# PM-BAT_v0_4-35X22_86.net
KiCad netlist of a schematic drawn in EAGLE
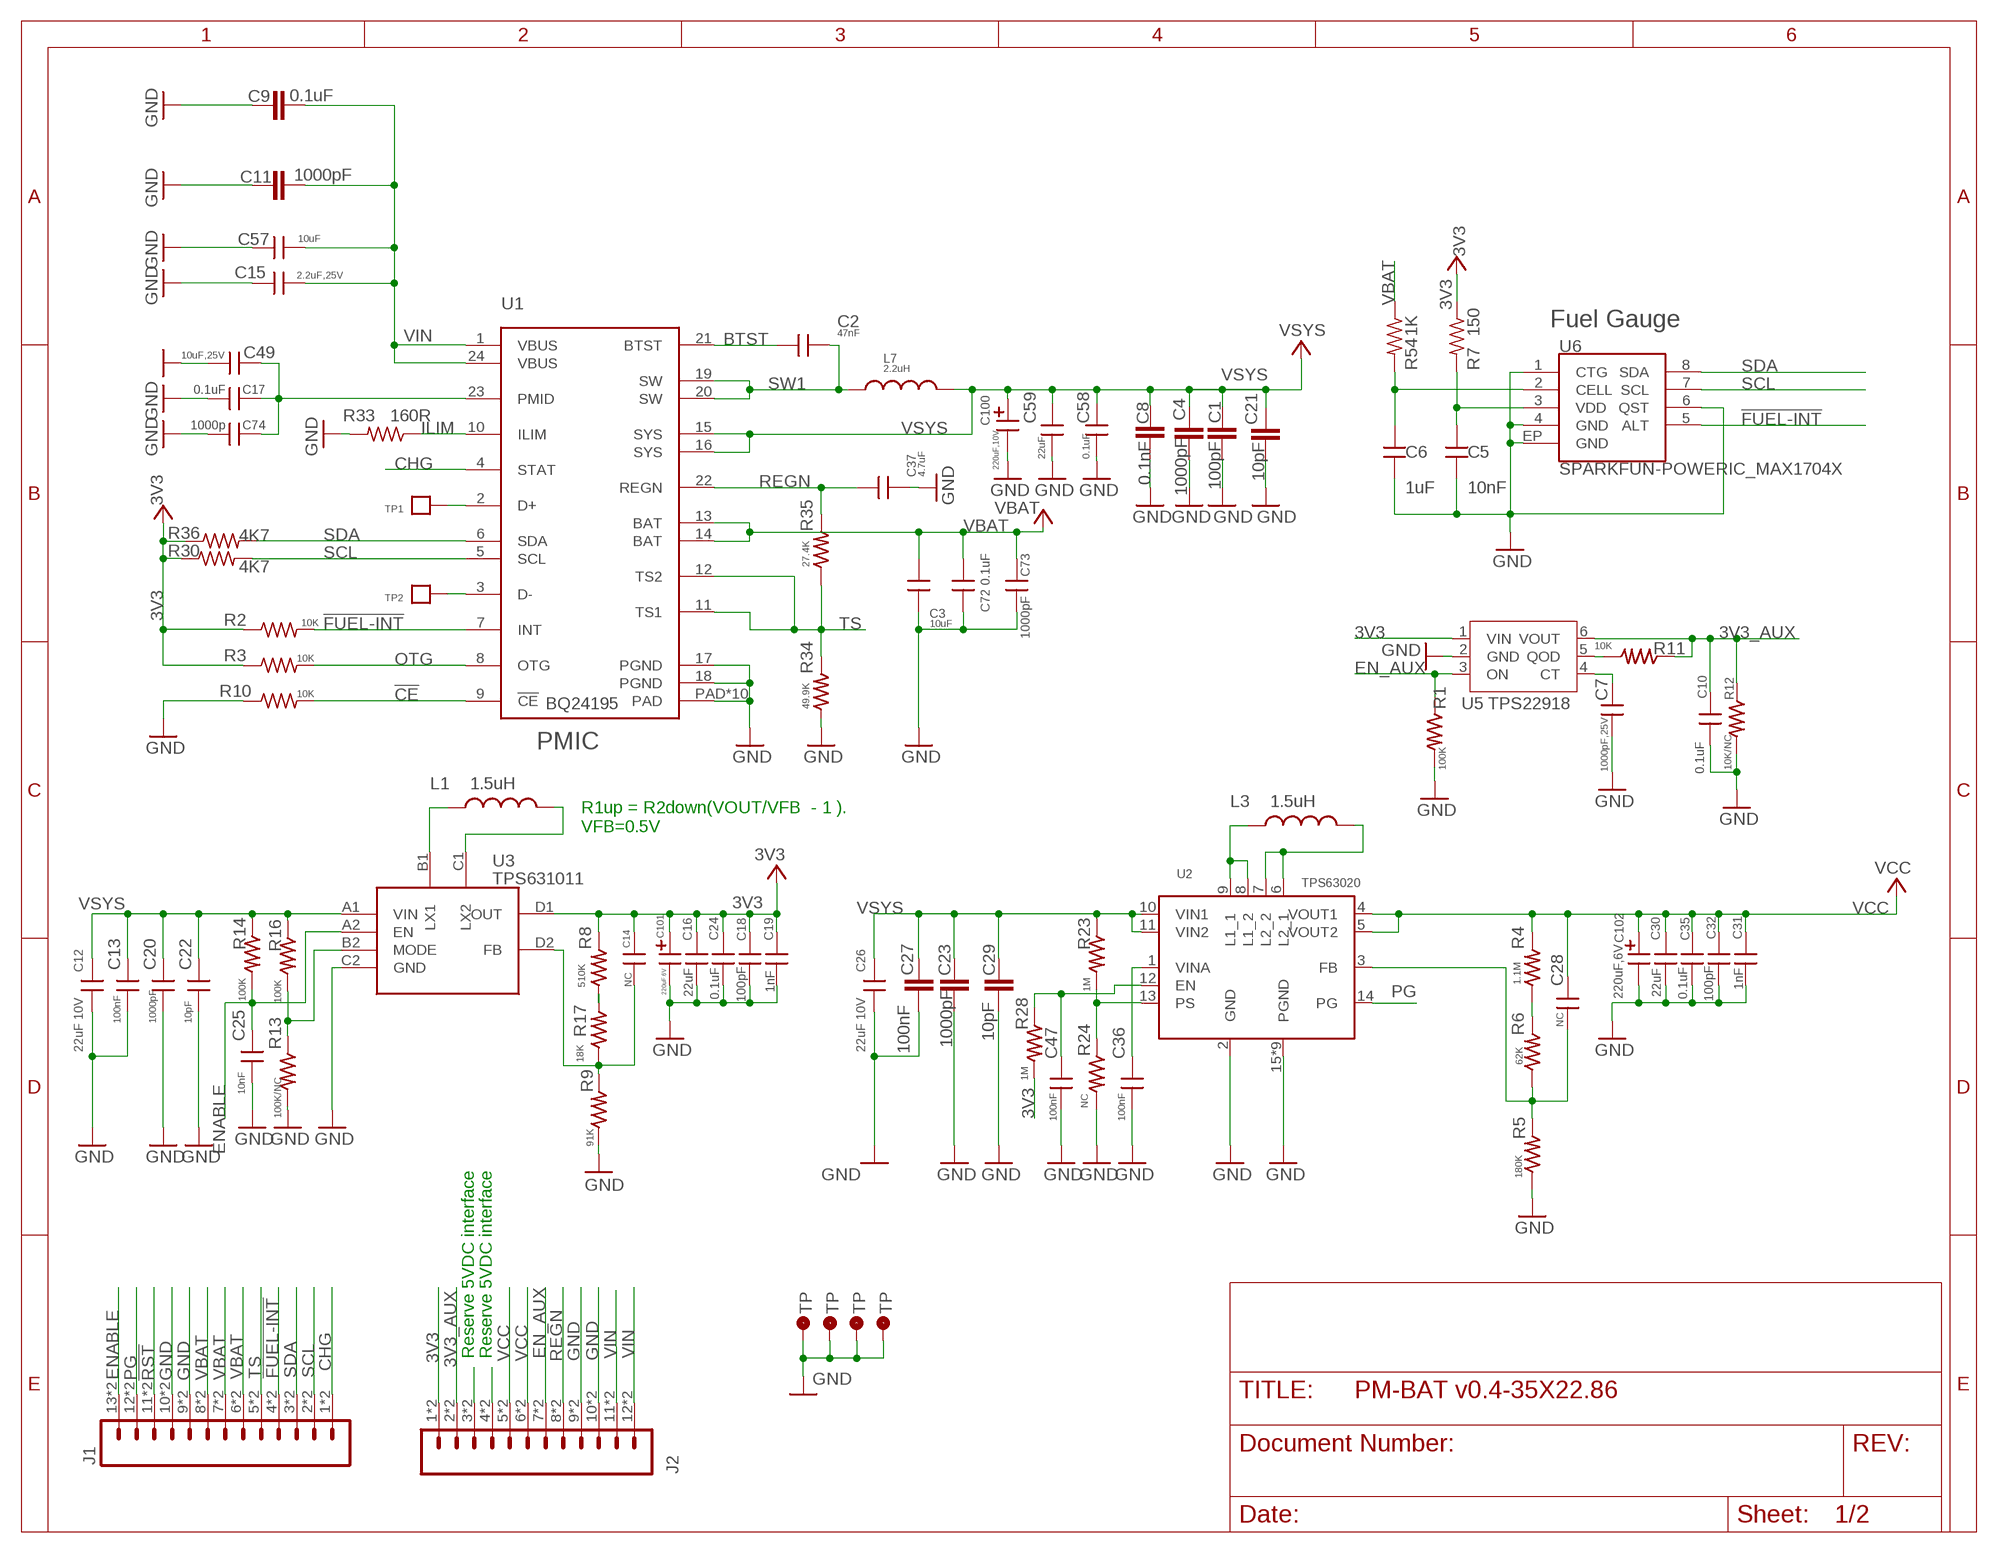
[diagram p0: schematic, sheet 1]

(export (version "E")
  (design (tool "Eeschema 10.0.6"))
  (components
    (comp (ref "C1")
      (value "100pF")
      (footprint "eagle-import:C0402_B")
      (libsource (lib "eagle-import") (part "CAP_1"))
    )
    (comp (ref "C2")
      (value "47nF")
      (footprint "eagle-import:C-0402")
      (libsource (lib "eagle-import") (part "particle SZ_CAP0402"))
    )
    (comp (ref "C3")
      (value "10uF")
      (footprint "eagle-import:C0805")
      (libsource (lib "eagle-import") (part "particle SZ_CAPC0805"))
    )
    (comp (ref "C4")
      (value "1000pF")
      (footprint "eagle-import:C0402_B")
      (libsource (lib "eagle-import") (part "CAP_1"))
    )
    (comp (ref "C5")
      (value "10nF")
      (footprint "eagle-import:C0402")
      (libsource (lib "eagle-import") (part "particle SZ_CAP0402A"))
    )
    (comp (ref "C6")
      (value "1uF")
      (footprint "eagle-import:C0402")
      (libsource (lib "eagle-import") (part "particle SZ_CAP0402A"))
    )
    (comp (ref "C7")
      (value "1000pF,25V")
      (footprint "eagle-import:C0402")
      (libsource (lib "eagle-import") (part "particle SZ_CAP0402A"))
    )
    (comp (ref "C8")
      (value "0.1nF")
      (footprint "eagle-import:C0402_B")
      (libsource (lib "eagle-import") (part "CAP_1"))
    )
    (comp (ref "C9")
      (value "0.1uF")
      (footprint "eagle-import:C0402_B")
      (libsource (lib "eagle-import") (part "CAP_1"))
    )
    (comp (ref "C10")
      (value "0.1uF")
      (footprint "eagle-import:C0201-N")
      (libsource (lib "eagle-import") (part "CAPC0201-N"))
    )
    (comp (ref "C11")
      (value "1000pF")
      (footprint "eagle-import:C0402_B")
      (libsource (lib "eagle-import") (part "CAP_1"))
    )
    (comp (ref "C12")
      (value "22uF 10V")
      (footprint "eagle-import:C0603")
      (libsource (lib "eagle-import") (part "particle SZ_21650216_CAPC0603"))
    )
    (comp (ref "C13")
      (value "100nF")
      (footprint "eagle-import:C0201-N")
      (libsource (lib "eagle-import") (part "CAPC0201-N"))
    )
    (comp (ref "C14")
      (value "NC")
      (footprint "eagle-import:C0201-N")
      (libsource (lib "eagle-import") (part "CAPC0201-N"))
    )
    (comp (ref "C15")
      (value "2.2uF,25V")
      (footprint "eagle-import:C-0603A")
      (libsource (lib "eagle-import") (part "particle SZ_CAP0603A"))
    )
    (comp (ref "C16")
      (value "22uF")
      (footprint "eagle-import:C-0603A")
      (libsource (lib "eagle-import") (part "particle SZ_21650216_CAP0603A"))
    )
    (comp (ref "C17")
      (value "0.1uF")
      (footprint "eagle-import:C0402")
      (libsource (lib "eagle-import") (part "CAP0402A"))
    )
    (comp (ref "C18")
      (value "100pF")
      (footprint "eagle-import:C0402")
      (libsource (lib "eagle-import") (part "particle SZ_CAP0402A"))
    )
    (comp (ref "C19")
      (value "1nF")
      (footprint "eagle-import:C0402")
      (libsource (lib "eagle-import") (part "particle SZ_CAP0402A"))
    )
    (comp (ref "C20")
      (value "1000pF")
      (footprint "eagle-import:C0201-N")
      (libsource (lib "eagle-import") (part "CAPC0201-N"))
    )
    (comp (ref "C21")
      (value "10pF")
      (footprint "eagle-import:C0402_B")
      (libsource (lib "eagle-import") (part "CAP_1"))
    )
    (comp (ref "C22")
      (value "10pF")
      (footprint "eagle-import:C0201-N")
      (libsource (lib "eagle-import") (part "CAPC0201-N"))
    )
    (comp (ref "C23")
      (value "1000pF")
      (footprint "eagle-import:C0402_B")
      (libsource (lib "eagle-import") (part "CAP_1"))
    )
    (comp (ref "C24")
      (value "0.1uF")
      (footprint "eagle-import:C0402")
      (libsource (lib "eagle-import") (part "particle SZ_CAP0402A"))
    )
    (comp (ref "C25")
      (value "10nF")
      (footprint "eagle-import:C0201-N")
      (libsource (lib "eagle-import") (part "CAPC0201-N"))
    )
    (comp (ref "C26")
      (value "22uF 10V")
      (footprint "eagle-import:C0603")
      (libsource (lib "eagle-import") (part "particle SZ_21650216_CAPC0603"))
    )
    (comp (ref "C27")
      (value "100nF")
      (footprint "eagle-import:C0402_B")
      (libsource (lib "eagle-import") (part "CAP_1"))
    )
    (comp (ref "C28")
      (value "NC")
      (footprint "eagle-import:C0201-N")
      (libsource (lib "eagle-import") (part "CAPC0201-N"))
    )
    (comp (ref "C29")
      (value "10pF")
      (footprint "eagle-import:C0402_B")
      (libsource (lib "eagle-import") (part "CAP_1"))
    )
    (comp (ref "C30")
      (value "22uF")
      (footprint "eagle-import:C-0603A")
      (libsource (lib "eagle-import") (part "particle SZ_21650216_CAP0603A"))
    )
    (comp (ref "C31")
      (value "1nF")
      (footprint "eagle-import:C0402")
      (libsource (lib "eagle-import") (part "particle SZ_CAP0402A"))
    )
    (comp (ref "C32")
      (value "100pF")
      (footprint "eagle-import:C0402")
      (libsource (lib "eagle-import") (part "particle SZ_CAP0402A"))
    )
    (comp (ref "C35")
      (value "0.1uF")
      (footprint "eagle-import:C0402")
      (libsource (lib "eagle-import") (part "particle SZ_CAP0402A"))
    )
    (comp (ref "C36")
      (value "100nF")
      (footprint "eagle-import:C0201-N")
      (libsource (lib "eagle-import") (part "CAPC0201-N"))
    )
    (comp (ref "C37")
      (value "4.7uF")
      (footprint "eagle-import:C0402")
      (libsource (lib "eagle-import") (part "particle SZ_CAP0402A"))
    )
    (comp (ref "C47")
      (value "100nF")
      (footprint "eagle-import:C0201-N")
      (libsource (lib "eagle-import") (part "CAPC0201-N"))
    )
    (comp (ref "C49")
      (value "10uF,25V")
      (footprint "eagle-import:C-0603A")
      (libsource (lib "eagle-import") (part "particle SZ_CAP0603A"))
    )
    (comp (ref "C57")
      (value "10uF")
      (footprint "eagle-import:C-0603A")
      (libsource (lib "eagle-import") (part "particle SZ_CAP0603A"))
    )
    (comp (ref "C58")
      (value "0.1uF")
      (footprint "eagle-import:C0402")
      (libsource (lib "eagle-import") (part "particle SZ_CAP0402A"))
    )
    (comp (ref "C59")
      (value "22uF")
      (footprint "eagle-import:C0603")
      (libsource (lib "eagle-import") (part "particle SZ_CAPC0603"))
    )
    (comp (ref "C72")
      (value "0.1uF")
      (footprint "eagle-import:C-0402")
      (libsource (lib "eagle-import") (part "particle SZ_CAP0402"))
    )
    (comp (ref "C73")
      (value "1000pF")
      (footprint "eagle-import:C-0402")
      (libsource (lib "eagle-import") (part "particle SZ_CAP0402"))
    )
    (comp (ref "C74")
      (value "1000p")
      (footprint "eagle-import:C-0402")
      (libsource (lib "eagle-import") (part "particle SZ_CAP0402"))
    )
    (comp (ref "C100")
      (value "220uF,10V")
      (footprint "eagle-import:CASE-B")
      (libsource (lib "eagle-import") (part "CAP-ECASE_B"))
    )
    (comp (ref "C101")
      (value "220uF.6V")
      (footprint "eagle-import:CASE-B")
      (libsource (lib "eagle-import") (part "CAP-ECASE_B"))
    )
    (comp (ref "C102")
      (value "220uF,6V")
      (footprint "eagle-import:CASE-B")
      (libsource (lib "eagle-import") (part "CAP-ECASE_B"))
    )
    (comp (ref "J1")
      (value "M13PTH-CST-R")
      (footprint "eagle-import:1X13-CASTELLATED")
      (libsource (lib "eagle-import") (part "M13PTH-CST-R"))
    )
    (comp (ref "J2")
      (value "M12PTH-CST-R")
      (footprint "eagle-import:1X12-CASTELLATED")
      (libsource (lib "eagle-import") (part "M12PTH-CST-R"))
    )
    (comp (ref "L1")
      (value "1.5uH")
      (footprint "eagle-import:INDUCTOR-2520")
      (libsource (lib "eagle-import") (part "INDUCTOR-SPARKFUNINDUCTOR-2520"))
    )
    (comp (ref "L3")
      (value "1.5uH")
      (footprint "eagle-import:INDUCTOR-2520")
      (libsource (lib "eagle-import") (part "INDUCTOR-SPARKFUNINDUCTOR-2520"))
    )
    (comp (ref "L7")
      (value "2.2uH")
      (footprint "eagle-import:INDUCTOR-4040")
      (libsource (lib "eagle-import") (part "INDUCTORI"))
    )
    (comp (ref "R1")
      (value "100K")
      (footprint "eagle-import:R0201-N")
      (libsource (lib "eagle-import") (part "RESR0201-N"))
    )
    (comp (ref "R2")
      (value "10K")
      (footprint "eagle-import:R0402_B")
      (libsource (lib "eagle-import") (part "Spark_R-US_"))
    )
    (comp (ref "R3")
      (value "10K")
      (footprint "eagle-import:R0402_B")
      (libsource (lib "eagle-import") (part "Spark_R-US_"))
    )
    (comp (ref "R4")
      (value "1.1M")
      (footprint "eagle-import:R0201-N")
      (libsource (lib "eagle-import") (part "RESR0201-N"))
    )
    (comp (ref "R5")
      (value "180K")
      (footprint "eagle-import:R0201-N")
      (libsource (lib "eagle-import") (part "RESR0201-N"))
    )
    (comp (ref "R6")
      (value "62K")
      (footprint "eagle-import:R0201-N")
      (libsource (lib "eagle-import") (part "RESR0201-N"))
    )
    (comp (ref "R7")
      (value "150")
      (footprint "eagle-import:R0402_B")
      (libsource (lib "eagle-import") (part "R-US_"))
    )
    (comp (ref "R8")
      (value "510K")
      (footprint "eagle-import:R0201-N")
      (libsource (lib "eagle-import") (part "RESR0201-N"))
    )
    (comp (ref "R9")
      (value "91K")
      (footprint "eagle-import:R0201-N")
      (libsource (lib "eagle-import") (part "RESR0201-N"))
    )
    (comp (ref "R10")
      (value "10K")
      (footprint "eagle-import:R0402_B")
      (libsource (lib "eagle-import") (part "Spark_R-US_"))
    )
    (comp (ref "R11")
      (value "10K")
      (footprint "eagle-import:R0201-N")
      (libsource (lib "eagle-import") (part "RESR0201-N"))
    )
    (comp (ref "R12")
      (value "10K/NC")
      (footprint "eagle-import:R0201-N")
      (libsource (lib "eagle-import") (part "RESR0201-N"))
    )
    (comp (ref "R13")
      (value "100K/NC")
      (footprint "eagle-import:R0201-N")
      (libsource (lib "eagle-import") (part "RESR0201-N"))
    )
    (comp (ref "R14")
      (value "100K")
      (footprint "eagle-import:R0201-N")
      (libsource (lib "eagle-import") (part "RESR0201-N"))
    )
    (comp (ref "R16")
      (value "100K")
      (footprint "eagle-import:R0201-N")
      (libsource (lib "eagle-import") (part "RESR0201-N"))
    )
    (comp (ref "R17")
      (value "18K")
      (footprint "eagle-import:R0201-N")
      (libsource (lib "eagle-import") (part "RESR0201-N"))
    )
    (comp (ref "R23")
      (value "1M")
      (footprint "eagle-import:R0201-N")
      (libsource (lib "eagle-import") (part "RESR0201-N"))
    )
    (comp (ref "R24")
      (value "NC")
      (footprint "eagle-import:R0201-N")
      (libsource (lib "eagle-import") (part "RESR0201-N"))
    )
    (comp (ref "R28")
      (value "1M")
      (footprint "eagle-import:R0201-N")
      (libsource (lib "eagle-import") (part "RESR0201-N"))
    )
    (comp (ref "R30")
      (value "4K7")
      (footprint "eagle-import:R0402_B")
      (libsource (lib "eagle-import") (part "R-US_"))
    )
    (comp (ref "R33")
      (value "160R")
      (footprint "eagle-import:R0402_B")
      (libsource (lib "eagle-import") (part "R-US_"))
    )
    (comp (ref "R34")
      (value "49.9K")
      (footprint "eagle-import:R0201-N")
      (libsource (lib "eagle-import") (part "RESR0201-N"))
    )
    (comp (ref "R35")
      (value "27.4K")
      (footprint "eagle-import:R0201-N")
      (libsource (lib "eagle-import") (part "RESR0201-N"))
    )
    (comp (ref "R36")
      (value "4K7")
      (footprint "eagle-import:R0402_B")
      (libsource (lib "eagle-import") (part "R-US_"))
    )
    (comp (ref "R54")
      (value "1K")
      (footprint "eagle-import:R0402_B")
      (libsource (lib "eagle-import") (part "R-US_"))
    )
    (comp (ref "TP1")
      (value "TP1311MM")
      (footprint "eagle-import:TP-1311MM")
      (libsource (lib "eagle-import") (part "TP1311MM"))
    )
    (comp (ref "TP2")
      (value "TP1311MM")
      (footprint "eagle-import:TP-1311MM")
      (libsource (lib "eagle-import") (part "TP1311MM"))
    )
    (comp (ref "U$1")
      (value "TP")
      (footprint "eagle-import:TP_2.33X1.37")
      (libsource (lib "eagle-import") (part "TP"))
    )
    (comp (ref "U$2")
      (value "TP")
      (footprint "eagle-import:TP_2.33X1.37")
      (libsource (lib "eagle-import") (part "TP"))
    )
    (comp (ref "U$4")
      (value "TP")
      (footprint "eagle-import:TP_2.33X1.37")
      (libsource (lib "eagle-import") (part "TP"))
    )
    (comp (ref "U$5")
      (value "TP")
      (footprint "eagle-import:TP_2.33X1.37")
      (libsource (lib "eagle-import") (part "TP"))
    )
    (comp (ref "U1")
      (value "BQ24195")
      (footprint "eagle-import:ELECTRON_QFN24")
      (libsource (lib "eagle-import") (part "ELECTRON_BQ24298RTWR"))
    )
    (comp (ref "U2")
      (value "TPS63020")
      (footprint "eagle-import:TPS63020")
      (libsource (lib "eagle-import") (part "TPS63020"))
    )
    (comp (ref "U3")
      (value "TPS631011")
      (footprint "eagle-import:DSBGA")
      (libsource (lib "eagle-import") (part "TPS631010"))
    )
    (comp (ref "U5")
      (value "TPS22918")
      (footprint "eagle-import:SOT-23-6")
      (libsource (lib "eagle-import") (part "TPS22918"))
    )
    (comp (ref "U6")
      (value "SPARKFUN-POWERIC_MAX1704X")
      (footprint "eagle-import:SPARKFUN-POWERIC_TDFN-8")
      (libsource (lib "eagle-import") (part "SPARKFUN-POWERIC_MAX1704X"))
    )
  )
  (nets
    (net (code "1") (name "3V3") (class "Default")
      (node (ref "C101") (pin "P$1") (pinfunction "1_P$1") (pintype "bidirectional"))
      (node (ref "C14") (pin "1") (pinfunction "1_1") (pintype "bidirectional"))
      (node (ref "C16") (pin "1") (pinfunction "1_1") (pintype "bidirectional"))
      (node (ref "C18") (pin "1") (pinfunction "1_1") (pintype "bidirectional"))
      (node (ref "C19") (pin "1") (pinfunction "1_1") (pintype "bidirectional"))
      (node (ref "C24") (pin "1") (pinfunction "1_1") (pintype "bidirectional"))
      (node (ref "J2") (pin "1") (pinfunction "1_1") (pintype "passive"))
      (node (ref "J2") (pin "@1") (pinfunction "1_@1") (pintype "passive"))
      (node (ref "R2") (pin "1") (pinfunction "1_1") (pintype "passive"))
      (node (ref "R28") (pin "2") (pinfunction "2_2") (pintype "bidirectional"))
      (node (ref "R3") (pin "1") (pinfunction "1_1") (pintype "passive"))
      (node (ref "R30") (pin "1") (pinfunction "1_1") (pintype "passive"))
      (node (ref "R36") (pin "1") (pinfunction "1_1") (pintype "passive"))
      (node (ref "R7") (pin "1") (pinfunction "1_1") (pintype "passive"))
      (node (ref "R8") (pin "2") (pinfunction "2_2") (pintype "bidirectional"))
      (node (ref "U3") (pin "D1") (pinfunction "OUT_D1") (pintype "bidirectional"))
      (node (ref "U5") (pin "1") (pinfunction "VIN_1") (pintype "bidirectional"))
    )
    (net (code "2") (name "3V3_AUX") (class "Default")
      (node (ref "C10") (pin "1") (pinfunction "1_1") (pintype "bidirectional"))
      (node (ref "J2") (pin "2") (pinfunction "2_2") (pintype "passive"))
      (node (ref "J2") (pin "@2") (pinfunction "2_@2") (pintype "passive"))
      (node (ref "R11") (pin "1") (pinfunction "1_1") (pintype "bidirectional"))
      (node (ref "R12") (pin "1") (pinfunction "1_1") (pintype "bidirectional"))
      (node (ref "U5") (pin "6") (pinfunction "VOUT_6") (pintype "bidirectional"))
    )
    (net (code "3") (name "BTST") (class "Default")
      (node (ref "C2") (pin "1") (pinfunction "1_1") (pintype "bidirectional"))
      (node (ref "U1") (pin "21") (pinfunction "BTST_21") (pintype "bidirectional"))
    )
    (net (code "4") (name "CHG") (class "Default")
      (node (ref "J1") (pin "1") (pinfunction "1_1") (pintype "passive"))
      (node (ref "J1") (pin "@1") (pinfunction "1_@1") (pintype "passive"))
      (node (ref "U1") (pin "4") (pinfunction "STAT_4") (pintype "bidirectional"))
    )
    (net (code "5") (name "ENABLE") (class "Default")
      (node (ref "C25") (pin "1") (pinfunction "1_1") (pintype "bidirectional"))
      (node (ref "J1") (pin "13") (pinfunction "13_13") (pintype "passive"))
      (node (ref "J1") (pin "@13") (pinfunction "13_@13") (pintype "passive"))
      (node (ref "R14") (pin "2") (pinfunction "2_2") (pintype "bidirectional"))
      (node (ref "U3") (pin "A2") (pinfunction "EN_A2") (pintype "bidirectional"))
    )
    (net (code "6") (name "EN_AUX") (class "Default")
      (node (ref "J2") (pin "7") (pinfunction "7_7") (pintype "passive"))
      (node (ref "J2") (pin "@7") (pinfunction "7_@7") (pintype "passive"))
      (node (ref "R1") (pin "1") (pinfunction "1_1") (pintype "bidirectional"))
      (node (ref "U5") (pin "3") (pinfunction "ON_3") (pintype "bidirectional"))
    )
    (net (code "7") (name "GND") (class "Default")
      (node (ref "C1") (pin "1") (pinfunction "P$1_1") (pintype "passive"))
      (node (ref "C10") (pin "2") (pinfunction "2_2") (pintype "bidirectional"))
      (node (ref "C100") (pin "P$2") (pinfunction "2_P$2") (pintype "bidirectional"))
      (node (ref "C101") (pin "P$2") (pinfunction "2_P$2") (pintype "bidirectional"))
      (node (ref "C102") (pin "P$2") (pinfunction "2_P$2") (pintype "bidirectional"))
      (node (ref "C11") (pin "1") (pinfunction "P$1_1") (pintype "passive"))
      (node (ref "C12") (pin "2") (pinfunction "2_2") (pintype "bidirectional"))
      (node (ref "C13") (pin "2") (pinfunction "2_2") (pintype "bidirectional"))
      (node (ref "C15") (pin "2") (pinfunction "2_2") (pintype "bidirectional"))
      (node (ref "C16") (pin "2") (pinfunction "2_2") (pintype "bidirectional"))
      (node (ref "C17") (pin "1") (pinfunction "1_1") (pintype "bidirectional"))
      (node (ref "C18") (pin "2") (pinfunction "2_2") (pintype "bidirectional"))
      (node (ref "C19") (pin "2") (pinfunction "2_2") (pintype "bidirectional"))
      (node (ref "C20") (pin "2") (pinfunction "2_2") (pintype "bidirectional"))
      (node (ref "C21") (pin "1") (pinfunction "P$1_1") (pintype "passive"))
      (node (ref "C22") (pin "2") (pinfunction "2_2") (pintype "bidirectional"))
      (node (ref "C23") (pin "1") (pinfunction "P$1_1") (pintype "passive"))
      (node (ref "C24") (pin "2") (pinfunction "2_2") (pintype "bidirectional"))
      (node (ref "C25") (pin "2") (pinfunction "2_2") (pintype "bidirectional"))
      (node (ref "C26") (pin "2") (pinfunction "2_2") (pintype "bidirectional"))
      (node (ref "C27") (pin "1") (pinfunction "P$1_1") (pintype "passive"))
      (node (ref "C29") (pin "1") (pinfunction "P$1_1") (pintype "passive"))
      (node (ref "C3") (pin "2") (pinfunction "2_2") (pintype "bidirectional"))
      (node (ref "C30") (pin "2") (pinfunction "2_2") (pintype "bidirectional"))
      (node (ref "C31") (pin "2") (pinfunction "2_2") (pintype "bidirectional"))
      (node (ref "C32") (pin "2") (pinfunction "2_2") (pintype "bidirectional"))
      (node (ref "C35") (pin "2") (pinfunction "2_2") (pintype "bidirectional"))
      (node (ref "C36") (pin "2") (pinfunction "2_2") (pintype "bidirectional"))
      (node (ref "C37") (pin "2") (pinfunction "2_2") (pintype "bidirectional"))
      (node (ref "C4") (pin "1") (pinfunction "P$1_1") (pintype "passive"))
      (node (ref "C47") (pin "2") (pinfunction "2_2") (pintype "bidirectional"))
      (node (ref "C49") (pin "2") (pinfunction "2_2") (pintype "bidirectional"))
      (node (ref "C5") (pin "2") (pinfunction "2_2") (pintype "bidirectional"))
      (node (ref "C57") (pin "2") (pinfunction "2_2") (pintype "bidirectional"))
      (node (ref "C58") (pin "2") (pinfunction "2_2") (pintype "bidirectional"))
      (node (ref "C59") (pin "2") (pinfunction "2_2") (pintype "bidirectional"))
      (node (ref "C6") (pin "2") (pinfunction "2_2") (pintype "bidirectional"))
      (node (ref "C7") (pin "2") (pinfunction "2_2") (pintype "bidirectional"))
      (node (ref "C72") (pin "2") (pinfunction "2_2") (pintype "bidirectional"))
      (node (ref "C73") (pin "2") (pinfunction "2_2") (pintype "bidirectional"))
      (node (ref "C74") (pin "1") (pinfunction "1_1") (pintype "bidirectional"))
      (node (ref "C8") (pin "1") (pinfunction "P$1_1") (pintype "passive"))
      (node (ref "C9") (pin "1") (pinfunction "P$1_1") (pintype "passive"))
      (node (ref "J1") (pin "10") (pinfunction "10_10") (pintype "passive"))
      (node (ref "J1") (pin "9") (pinfunction "9_9") (pintype "passive"))
      (node (ref "J1") (pin "@10") (pinfunction "10_@10") (pintype "passive"))
      (node (ref "J1") (pin "@9") (pinfunction "9_@9") (pintype "passive"))
      (node (ref "J2") (pin "10") (pinfunction "10_10") (pintype "passive"))
      (node (ref "J2") (pin "9") (pinfunction "9_9") (pintype "passive"))
      (node (ref "J2") (pin "@10") (pinfunction "10_@10") (pintype "passive"))
      (node (ref "J2") (pin "@9") (pinfunction "9_@9") (pintype "passive"))
      (node (ref "R1") (pin "2") (pinfunction "2_2") (pintype "bidirectional"))
      (node (ref "R10") (pin "1") (pinfunction "1_1") (pintype "passive"))
      (node (ref "R12") (pin "2") (pinfunction "2_2") (pintype "bidirectional"))
      (node (ref "R13") (pin "2") (pinfunction "2_2") (pintype "bidirectional"))
      (node (ref "R24") (pin "2") (pinfunction "2_2") (pintype "bidirectional"))
      (node (ref "R33") (pin "2") (pinfunction "2_2") (pintype "passive"))
      (node (ref "R34") (pin "1") (pinfunction "1_1") (pintype "bidirectional"))
      (node (ref "R5") (pin "1") (pinfunction "1_1") (pintype "bidirectional"))
      (node (ref "R9") (pin "1") (pinfunction "1_1") (pintype "bidirectional"))
      (node (ref "U$1") (pin "1") (pinfunction "TP_1") (pintype "bidirectional"))
      (node (ref "U$2") (pin "1") (pinfunction "TP_1") (pintype "bidirectional"))
      (node (ref "U$4") (pin "1") (pinfunction "TP_1") (pintype "bidirectional"))
      (node (ref "U$5") (pin "1") (pinfunction "TP_1") (pintype "bidirectional"))
      (node (ref "U1") (pin "17") (pinfunction "PGND_17") (pintype "passive"))
      (node (ref "U1") (pin "18") (pinfunction "PGND_18") (pintype "passive"))
      (node (ref "U1") (pin "PAD") (pinfunction "PAD_PAD") (pintype "power_in"))
      (node (ref "U1") (pin "PAD@1") (pinfunction "PAD_PAD@1") (pintype "power_in"))
      (node (ref "U1") (pin "PAD@2") (pinfunction "PAD_PAD@2") (pintype "power_in"))
      (node (ref "U1") (pin "PAD@3") (pinfunction "PAD_PAD@3") (pintype "power_in"))
      (node (ref "U1") (pin "PAD@4") (pinfunction "PAD_PAD@4") (pintype "power_in"))
      (node (ref "U1") (pin "PAD@5") (pinfunction "PAD_PAD@5") (pintype "power_in"))
      (node (ref "U1") (pin "PAD@6") (pinfunction "PAD_PAD@6") (pintype "power_in"))
      (node (ref "U1") (pin "PAD@7") (pinfunction "PAD_PAD@7") (pintype "power_in"))
      (node (ref "U1") (pin "PAD@8") (pinfunction "PAD_PAD@8") (pintype "power_in"))
      (node (ref "U1") (pin "PAD@9") (pinfunction "PAD_PAD@9") (pintype "power_in"))
      (node (ref "U2") (pin "15") (pinfunction "PGND_15") (pintype "bidirectional"))
      (node (ref "U2") (pin "16") (pinfunction "PGND_16") (pintype "bidirectional"))
      (node (ref "U2") (pin "17") (pinfunction "PGND_17") (pintype "bidirectional"))
      (node (ref "U2") (pin "18") (pinfunction "PGND_18") (pintype "bidirectional"))
      (node (ref "U2") (pin "19") (pinfunction "PGND_19") (pintype "bidirectional"))
      (node (ref "U2") (pin "2") (pinfunction "GND_2") (pintype "bidirectional"))
      (node (ref "U2") (pin "20") (pinfunction "PGND_20") (pintype "bidirectional"))
      (node (ref "U2") (pin "21") (pinfunction "PGND_21") (pintype "bidirectional"))
      (node (ref "U2") (pin "22") (pinfunction "PGND_22") (pintype "bidirectional"))
      (node (ref "U2") (pin "23") (pinfunction "PGND_23") (pintype "bidirectional"))
      (node (ref "U3") (pin "C2") (pinfunction "GND_C2") (pintype "bidirectional"))
      (node (ref "U5") (pin "2") (pinfunction "GND_2") (pintype "bidirectional"))
      (node (ref "U6") (pin "1") (pinfunction "CTG_1") (pintype "bidirectional"))
      (node (ref "U6") (pin "4") (pinfunction "GND_4") (pintype "bidirectional"))
      (node (ref "U6") (pin "6") (pinfunction "QST_6") (pintype "bidirectional"))
      (node (ref "U6") (pin "EP") (pinfunction "GND_EP") (pintype "bidirectional"))
    )
    (net (code "8") (name "ILIM") (class "Default")
      (node (ref "R33") (pin "1") (pinfunction "1_1") (pintype "passive"))
      (node (ref "U1") (pin "10") (pinfunction "ILIM_10") (pintype "output"))
    )
    (net (code "9") (name "Net-(J2-3-Pad@3)") (class "Default")
      (node (ref "J2") (pin "3") (pinfunction "3_3") (pintype "passive"))
      (node (ref "J2") (pin "@3") (pinfunction "3_@3") (pintype "passive"))
    )
    (net (code "10") (name "Net-(J2-4-Pad@4)") (class "Default")
      (node (ref "J2") (pin "4") (pinfunction "4_4") (pintype "passive"))
      (node (ref "J2") (pin "@4") (pinfunction "4_@4") (pintype "passive"))
    )
    (net (code "11") (name "Net-(R4-Pad1)") (class "Default")
      (node (ref "R4") (pin "1") (pinfunction "1_1") (pintype "bidirectional"))
      (node (ref "R6") (pin "2") (pinfunction "2_2") (pintype "bidirectional"))
    )
    (net (code "12") (name "Net-(R17-Pad2)") (class "Default")
      (node (ref "R17") (pin "2") (pinfunction "2_2") (pintype "bidirectional"))
      (node (ref "R8") (pin "1") (pinfunction "1_1") (pintype "bidirectional"))
    )
    (net (code "13") (name "Net-(TP1-1)") (class "Default")
      (node (ref "TP1") (pin "P$1") (pinfunction "1_P$1") (pintype "bidirectional"))
      (node (ref "U1") (pin "2") (pinfunction "D+_2") (pintype "output"))
    )
    (net (code "14") (name "Net-(TP2-1)") (class "Default")
      (node (ref "TP2") (pin "P$1") (pinfunction "1_P$1") (pintype "bidirectional"))
      (node (ref "U1") (pin "3") (pinfunction "D-_3") (pintype "output"))
    )
    (net (code "15") (name "Net-(U1-PMID)") (class "Default")
      (node (ref "C17") (pin "2") (pinfunction "2_2") (pintype "bidirectional"))
      (node (ref "C49") (pin "1") (pinfunction "1_1") (pintype "bidirectional"))
      (node (ref "C74") (pin "2") (pinfunction "2_2") (pintype "bidirectional"))
      (node (ref "U1") (pin "23") (pinfunction "PMID_23") (pintype "passive"))
    )
    (net (code "16") (name "Net-(U2-EN)") (class "Default")
      (node (ref "C47") (pin "1") (pinfunction "1_1") (pintype "bidirectional"))
      (node (ref "R28") (pin "1") (pinfunction "1_1") (pintype "bidirectional"))
      (node (ref "U2") (pin "12") (pinfunction "EN_12") (pintype "bidirectional"))
    )
    (net (code "17") (name "Net-(U2-FB)") (class "Default")
      (node (ref "C28") (pin "2") (pinfunction "2_2") (pintype "bidirectional"))
      (node (ref "R5") (pin "2") (pinfunction "2_2") (pintype "bidirectional"))
      (node (ref "R6") (pin "1") (pinfunction "1_1") (pintype "bidirectional"))
      (node (ref "U2") (pin "3") (pinfunction "FB_3") (pintype "bidirectional"))
    )
    (net (code "18") (name "Net-(U2-L1_1)") (class "Default")
      (node (ref "L3") (pin "1") (pinfunction "1_1") (pintype "passive"))
      (node (ref "U2") (pin "8") (pinfunction "L1_2_8") (pintype "bidirectional"))
      (node (ref "U2") (pin "9") (pinfunction "L1_1_9") (pintype "bidirectional"))
    )
    (net (code "19") (name "Net-(U2-L2_1)") (class "Default")
      (node (ref "L3") (pin "2") (pinfunction "2_2") (pintype "passive"))
      (node (ref "U2") (pin "6") (pinfunction "L2_1_6") (pintype "bidirectional"))
      (node (ref "U2") (pin "7") (pinfunction "L2_2_7") (pintype "bidirectional"))
    )
    (net (code "20") (name "Net-(U2-PS)") (class "Default")
      (node (ref "R23") (pin "2") (pinfunction "2_2") (pintype "bidirectional"))
      (node (ref "R24") (pin "1") (pinfunction "1_1") (pintype "bidirectional"))
      (node (ref "U2") (pin "13") (pinfunction "PS_13") (pintype "bidirectional"))
    )
    (net (code "21") (name "Net-(U2-VINA)") (class "Default")
      (node (ref "C36") (pin "1") (pinfunction "1_1") (pintype "bidirectional"))
      (node (ref "U2") (pin "1") (pinfunction "VINA_1") (pintype "bidirectional"))
    )
    (net (code "22") (name "Net-(U3-FB)") (class "Default")
      (node (ref "C14") (pin "2") (pinfunction "2_2") (pintype "bidirectional"))
      (node (ref "R17") (pin "1") (pinfunction "1_1") (pintype "bidirectional"))
      (node (ref "R9") (pin "2") (pinfunction "2_2") (pintype "bidirectional"))
      (node (ref "U3") (pin "D2") (pinfunction "FB_D2") (pintype "bidirectional"))
    )
    (net (code "23") (name "Net-(U3-LX1)") (class "Default")
      (node (ref "L1") (pin "1") (pinfunction "1_1") (pintype "passive"))
      (node (ref "U3") (pin "B1") (pinfunction "LX1_B1") (pintype "bidirectional"))
    )
    (net (code "24") (name "Net-(U3-LX2)") (class "Default")
      (node (ref "L1") (pin "2") (pinfunction "2_2") (pintype "passive"))
      (node (ref "U3") (pin "C1") (pinfunction "LX2_C1") (pintype "bidirectional"))
    )
    (net (code "25") (name "Net-(U3-MODE)") (class "Default")
      (node (ref "R13") (pin "1") (pinfunction "1_1") (pintype "bidirectional"))
      (node (ref "R16") (pin "2") (pinfunction "2_2") (pintype "bidirectional"))
      (node (ref "U3") (pin "B2") (pinfunction "MODE_B2") (pintype "bidirectional"))
    )
    (net (code "26") (name "Net-(U5-CT)") (class "Default")
      (node (ref "C7") (pin "1") (pinfunction "1_1") (pintype "bidirectional"))
      (node (ref "U5") (pin "4") (pinfunction "CT_4") (pintype "bidirectional"))
    )
    (net (code "27") (name "Net-(U5-QOD)") (class "Default")
      (node (ref "R11") (pin "2") (pinfunction "2_2") (pintype "bidirectional"))
      (node (ref "U5") (pin "5") (pinfunction "QOD_5") (pintype "bidirectional"))
    )
    (net (code "28") (name "Net-(U6-CELL)") (class "Default")
      (node (ref "C6") (pin "1") (pinfunction "1_1") (pintype "bidirectional"))
      (node (ref "R54") (pin "2") (pinfunction "2_2") (pintype "passive"))
      (node (ref "U6") (pin "2") (pinfunction "CELL_2") (pintype "bidirectional"))
    )
    (net (code "29") (name "Net-(U6-VDD)") (class "Default")
      (node (ref "C5") (pin "1") (pinfunction "1_1") (pintype "bidirectional"))
      (node (ref "R7") (pin "2") (pinfunction "2_2") (pintype "passive"))
      (node (ref "U6") (pin "3") (pinfunction "VDD_3") (pintype "bidirectional"))
    )
    (net (code "30") (name "OTG") (class "Default")
      (node (ref "R3") (pin "2") (pinfunction "2_2") (pintype "passive"))
      (node (ref "U1") (pin "8") (pinfunction "OTG_8") (pintype "bidirectional"))
    )
    (net (code "31") (name "PG") (class "Default")
      (node (ref "J1") (pin "12") (pinfunction "12_12") (pintype "passive"))
      (node (ref "J1") (pin "@12") (pinfunction "12_@12") (pintype "passive"))
      (node (ref "U2") (pin "14") (pinfunction "PG_14") (pintype "bidirectional"))
    )
    (net (code "32") (name "REGN") (class "Default")
      (node (ref "C37") (pin "1") (pinfunction "1_1") (pintype "bidirectional"))
      (node (ref "J2") (pin "8") (pinfunction "8_8") (pintype "passive"))
      (node (ref "J2") (pin "@8") (pinfunction "8_@8") (pintype "passive"))
      (node (ref "R35") (pin "2") (pinfunction "2_2") (pintype "bidirectional"))
      (node (ref "U1") (pin "22") (pinfunction "REGN_22") (pintype "bidirectional"))
    )
    (net (code "33") (name "SCL") (class "Default")
      (node (ref "J1") (pin "2") (pinfunction "2_2") (pintype "passive"))
      (node (ref "J1") (pin "@2") (pinfunction "2_@2") (pintype "passive"))
      (node (ref "R30") (pin "2") (pinfunction "2_2") (pintype "passive"))
      (node (ref "U1") (pin "5") (pinfunction "SCL_5") (pintype "output"))
      (node (ref "U6") (pin "7") (pinfunction "SCL_7") (pintype "bidirectional"))
    )
    (net (code "34") (name "SDA") (class "Default")
      (node (ref "J1") (pin "3") (pinfunction "3_3") (pintype "passive"))
      (node (ref "J1") (pin "@3") (pinfunction "3_@3") (pintype "passive"))
      (node (ref "R36") (pin "2") (pinfunction "2_2") (pintype "passive"))
      (node (ref "U1") (pin "6") (pinfunction "SDA_6") (pintype "bidirectional"))
      (node (ref "U6") (pin "8") (pinfunction "SDA_8") (pintype "bidirectional"))
    )
    (net (code "35") (name "SW1") (class "Default")
      (node (ref "C2") (pin "2") (pinfunction "2_2") (pintype "bidirectional"))
      (node (ref "L7") (pin "P$1") (pinfunction "1_P$1") (pintype "passive"))
      (node (ref "U1") (pin "19") (pinfunction "SW_19") (pintype "power_in"))
      (node (ref "U1") (pin "20") (pinfunction "SW_20") (pintype "power_in"))
    )
    (net (code "36") (name "TS") (class "Default")
      (node (ref "J1") (pin "5") (pinfunction "5_5") (pintype "passive"))
      (node (ref "J1") (pin "@5") (pinfunction "5_@5") (pintype "passive"))
      (node (ref "R34") (pin "2") (pinfunction "2_2") (pintype "bidirectional"))
      (node (ref "R35") (pin "1") (pinfunction "1_1") (pintype "bidirectional"))
      (node (ref "U1") (pin "11") (pinfunction "TS1_11") (pintype "bidirectional"))
      (node (ref "U1") (pin "12") (pinfunction "TS2_12") (pintype "bidirectional"))
    )
    (net (code "37") (name "VBAT") (class "Default")
      (node (ref "C3") (pin "1") (pinfunction "1_1") (pintype "bidirectional"))
      (node (ref "C72") (pin "1") (pinfunction "1_1") (pintype "bidirectional"))
      (node (ref "C73") (pin "1") (pinfunction "1_1") (pintype "bidirectional"))
      (node (ref "J1") (pin "6") (pinfunction "6_6") (pintype "passive"))
      (node (ref "J1") (pin "7") (pinfunction "7_7") (pintype "passive"))
      (node (ref "J1") (pin "8") (pinfunction "8_8") (pintype "passive"))
      (node (ref "J1") (pin "@6") (pinfunction "6_@6") (pintype "passive"))
      (node (ref "J1") (pin "@7") (pinfunction "7_@7") (pintype "passive"))
      (node (ref "J1") (pin "@8") (pinfunction "8_@8") (pintype "passive"))
      (node (ref "R54") (pin "1") (pinfunction "1_1") (pintype "passive"))
      (node (ref "U1") (pin "13") (pinfunction "BAT_13") (pintype "passive"))
      (node (ref "U1") (pin "14") (pinfunction "BAT_14") (pintype "power_in"))
    )
    (net (code "38") (name "VCC") (class "Default")
      (node (ref "C102") (pin "P$1") (pinfunction "1_P$1") (pintype "bidirectional"))
      (node (ref "C28") (pin "1") (pinfunction "1_1") (pintype "bidirectional"))
      (node (ref "C30") (pin "1") (pinfunction "1_1") (pintype "bidirectional"))
      (node (ref "C31") (pin "1") (pinfunction "1_1") (pintype "bidirectional"))
      (node (ref "C32") (pin "1") (pinfunction "1_1") (pintype "bidirectional"))
      (node (ref "C35") (pin "1") (pinfunction "1_1") (pintype "bidirectional"))
      (node (ref "J2") (pin "5") (pinfunction "5_5") (pintype "passive"))
      (node (ref "J2") (pin "6") (pinfunction "6_6") (pintype "passive"))
      (node (ref "J2") (pin "@5") (pinfunction "5_@5") (pintype "passive"))
      (node (ref "J2") (pin "@6") (pinfunction "6_@6") (pintype "passive"))
      (node (ref "R4") (pin "2") (pinfunction "2_2") (pintype "bidirectional"))
      (node (ref "U2") (pin "4") (pinfunction "VOUT1_4") (pintype "bidirectional"))
      (node (ref "U2") (pin "5") (pinfunction "VOUT2_5") (pintype "bidirectional"))
    )
    (net (code "39") (name "VIN") (class "Default")
      (node (ref "C11") (pin "2") (pinfunction "P$2_2") (pintype "passive"))
      (node (ref "C15") (pin "1") (pinfunction "1_1") (pintype "bidirectional"))
      (node (ref "C57") (pin "1") (pinfunction "1_1") (pintype "bidirectional"))
      (node (ref "C9") (pin "2") (pinfunction "P$2_2") (pintype "passive"))
      (node (ref "J2") (pin "11") (pinfunction "11_11") (pintype "passive"))
      (node (ref "J2") (pin "12") (pinfunction "12_12") (pintype "passive"))
      (node (ref "J2") (pin "@11") (pinfunction "11_@11") (pintype "passive"))
      (node (ref "J2") (pin "@12") (pinfunction "12_@12") (pintype "passive"))
      (node (ref "U1") (pin "1") (pinfunction "VBUS_1") (pintype "power_in"))
      (node (ref "U1") (pin "24") (pinfunction "VBUS_24") (pintype "passive"))
    )
    (net (code "40") (name "VSYS") (class "Default")
      (node (ref "C1") (pin "2") (pinfunction "P$2_2") (pintype "passive"))
      (node (ref "C100") (pin "P$1") (pinfunction "1_P$1") (pintype "bidirectional"))
      (node (ref "C12") (pin "1") (pinfunction "1_1") (pintype "bidirectional"))
      (node (ref "C13") (pin "1") (pinfunction "1_1") (pintype "bidirectional"))
      (node (ref "C20") (pin "1") (pinfunction "1_1") (pintype "bidirectional"))
      (node (ref "C21") (pin "2") (pinfunction "P$2_2") (pintype "passive"))
      (node (ref "C22") (pin "1") (pinfunction "1_1") (pintype "bidirectional"))
      (node (ref "C23") (pin "2") (pinfunction "P$2_2") (pintype "passive"))
      (node (ref "C26") (pin "1") (pinfunction "1_1") (pintype "bidirectional"))
      (node (ref "C27") (pin "2") (pinfunction "P$2_2") (pintype "passive"))
      (node (ref "C29") (pin "2") (pinfunction "P$2_2") (pintype "passive"))
      (node (ref "C4") (pin "2") (pinfunction "P$2_2") (pintype "passive"))
      (node (ref "C58") (pin "1") (pinfunction "1_1") (pintype "bidirectional"))
      (node (ref "C59") (pin "1") (pinfunction "1_1") (pintype "bidirectional"))
      (node (ref "C8") (pin "2") (pinfunction "P$2_2") (pintype "passive"))
      (node (ref "L7") (pin "P$2") (pinfunction "2_P$2") (pintype "passive"))
      (node (ref "R14") (pin "1") (pinfunction "1_1") (pintype "bidirectional"))
      (node (ref "R16") (pin "1") (pinfunction "1_1") (pintype "bidirectional"))
      (node (ref "R23") (pin "1") (pinfunction "1_1") (pintype "bidirectional"))
      (node (ref "U1") (pin "15") (pinfunction "SYS_15") (pintype "power_in"))
      (node (ref "U1") (pin "16") (pinfunction "SYS_16") (pintype "power_in"))
      (node (ref "U2") (pin "10") (pinfunction "VIN1_10") (pintype "bidirectional"))
      (node (ref "U2") (pin "11") (pinfunction "VIN2_11") (pintype "bidirectional"))
      (node (ref "U3") (pin "A1") (pinfunction "VIN_A1") (pintype "bidirectional"))
    )
    (net (code "41") (name "~{CE}") (class "Default")
      (node (ref "R10") (pin "2") (pinfunction "2_2") (pintype "passive"))
      (node (ref "U1") (pin "9") (pinfunction "~{CE}_9") (pintype "output"))
    )
    (net (code "42") (name "~{FUEL-INT}") (class "Default")
      (node (ref "J1") (pin "4") (pinfunction "4_4") (pintype "passive"))
      (node (ref "J1") (pin "@4") (pinfunction "4_@4") (pintype "passive"))
      (node (ref "R2") (pin "2") (pinfunction "2_2") (pintype "passive"))
      (node (ref "U1") (pin "7") (pinfunction "INT_7") (pintype "bidirectional"))
      (node (ref "U6") (pin "5") (pinfunction "ALT_5") (pintype "bidirectional"))
    )
    (net (code "43") (name "~{RST}") (class "Default")
      (node (ref "J1") (pin "11") (pinfunction "11_11") (pintype "passive"))
      (node (ref "J1") (pin "@11") (pinfunction "11_@11") (pintype "passive"))
    )
  )
)
